# bubbledisplayfrontpack_v02.net
KiCad netlist of a schematic drawn in EAGLE
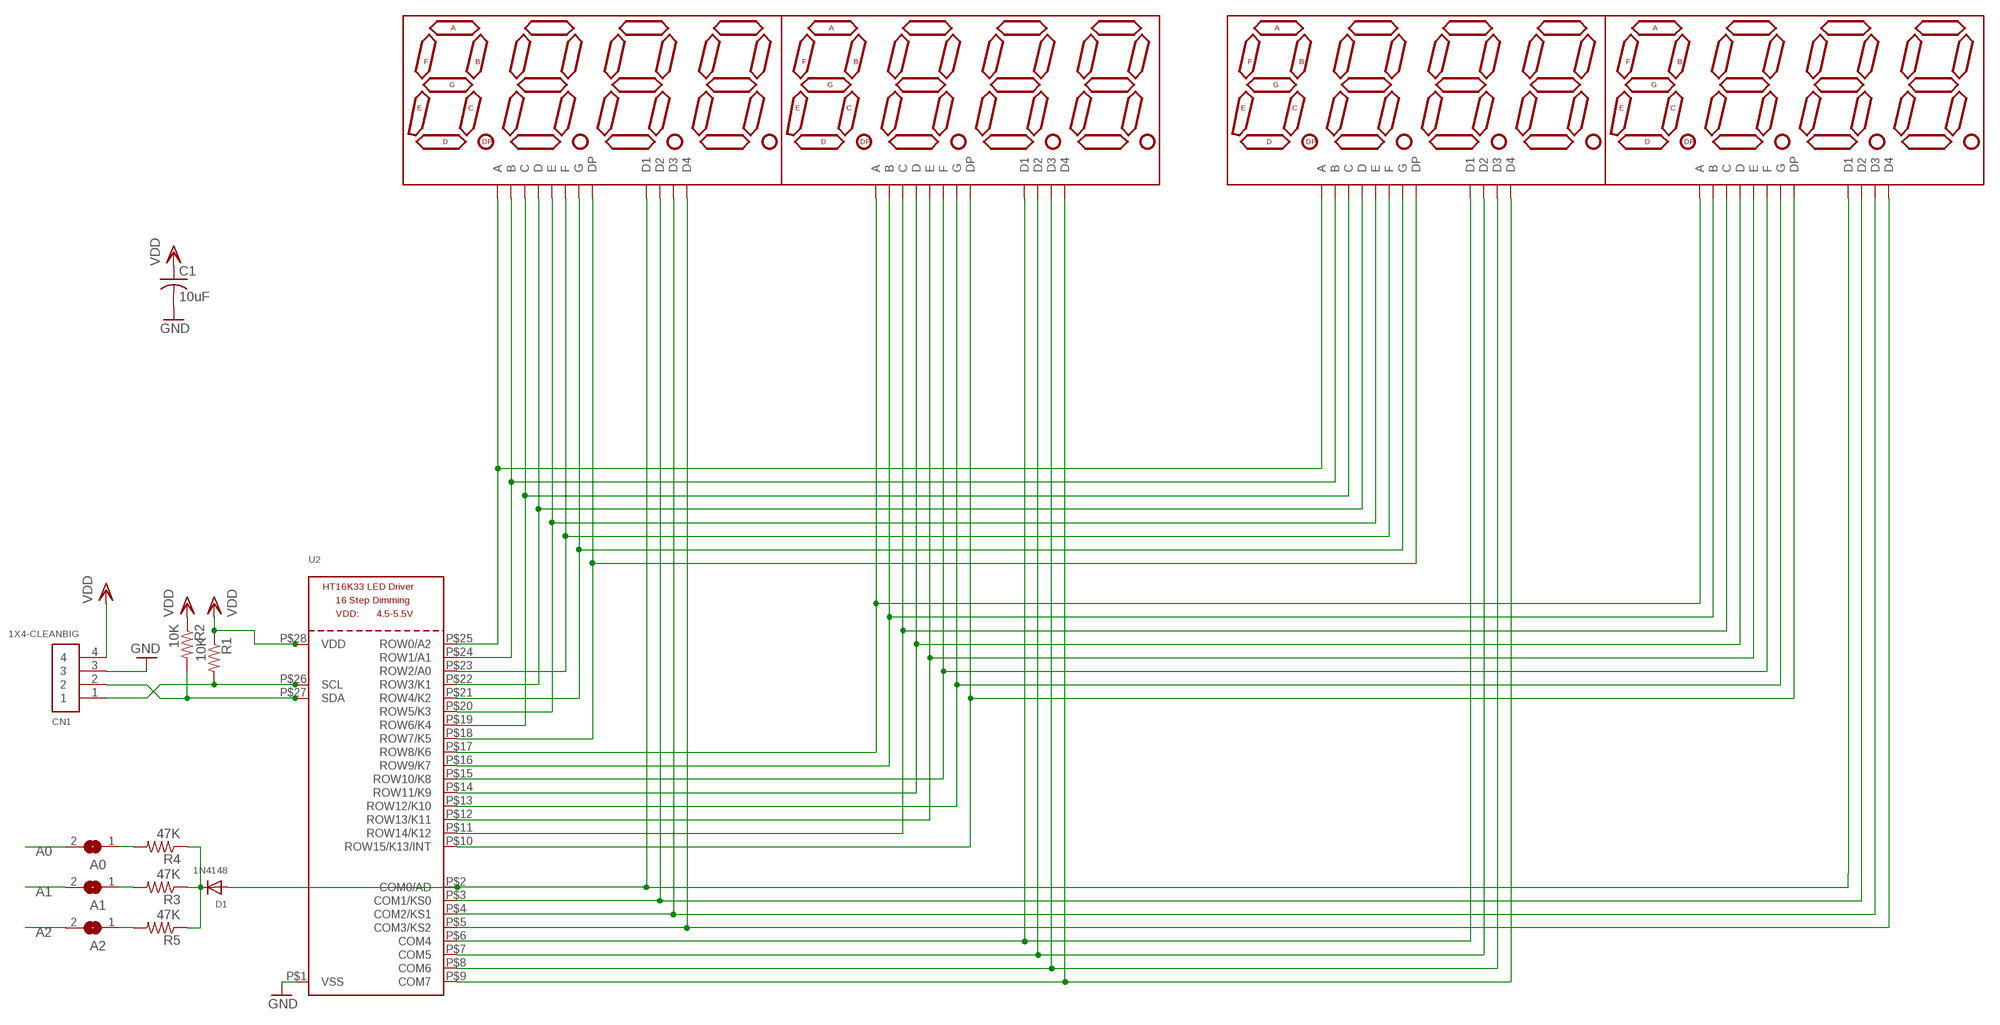
[diagram p0: schematic, sheet 1]

(export (version "E")
  (design (tool "Eeschema 10.0.6"))
  (components
    (comp (ref "A0")
      (value "SOLDERJUMPERREFLOW_NOPASTE")
      (footprint "eagle-import:SOLDERJUMPER_REFLOW_NOPASTE")
      (libsource (lib "eagle-import") (part "SOLDERJUMPERREFLOW_NOPASTE"))
    )
    (comp (ref "A1")
      (value "SOLDERJUMPERREFLOW_NOPASTE")
      (footprint "eagle-import:SOLDERJUMPER_REFLOW_NOPASTE")
      (libsource (lib "eagle-import") (part "SOLDERJUMPERREFLOW_NOPASTE"))
    )
    (comp (ref "A2")
      (value "SOLDERJUMPERREFLOW_NOPASTE")
      (footprint "eagle-import:SOLDERJUMPER_REFLOW_NOPASTE")
      (libsource (lib "eagle-import") (part "SOLDERJUMPERREFLOW_NOPASTE"))
    )
    (comp (ref "C1")
      (value "10uF")
      (footprint "eagle-import:C0805K")
      (libsource (lib "eagle-import") (part "C-USC0805K"))
    )
    (comp (ref "CN1")
      (value "1X4-CLEANBIG")
      (footprint "eagle-import:1X04-CLEANBIG")
      (libsource (lib "eagle-import") (part "1X4-CLEANBIG"))
    )
    (comp (ref "D1")
      (value "1N4148")
      (footprint "eagle-import:SOD-323F")
      (libsource (lib "eagle-import") (part "DIODESOD-323F"))
    )
    (comp (ref "DISPLAY1")
      (value "hp")
      (footprint "eagle-import:DIL12")
      (libsource (lib "eagle-import") (part "7-SEGMENT-4DIGIT-COUNTER-HP-BUBBLE"))
    )
    (comp (ref "DISPLAY2")
      (value "hp")
      (footprint "eagle-import:DIL12")
      (libsource (lib "eagle-import") (part "7-SEGMENT-4DIGIT-COUNTER-HP-BUBBLE"))
    )
    (comp (ref "DISPLAY3")
      (value "hp")
      (footprint "eagle-import:DIL12")
      (libsource (lib "eagle-import") (part "7-SEGMENT-4DIGIT-COUNTER-HP-BUBBLE"))
    )
    (comp (ref "DISPLAY4")
      (value "hp")
      (footprint "eagle-import:DIL12")
      (libsource (lib "eagle-import") (part "7-SEGMENT-4DIGIT-COUNTER-HP-BUBBLE"))
    )
    (comp (ref "R1")
      (value "10K")
      (footprint "eagle-import:R0805")
      (libsource (lib "eagle-import") (part "R-US_R0805"))
    )
    (comp (ref "R2")
      (value "10K")
      (footprint "eagle-import:R0805")
      (libsource (lib "eagle-import") (part "R-US_R0805"))
    )
    (comp (ref "R3")
      (value "47K")
      (footprint "eagle-import:R0805")
      (libsource (lib "eagle-import") (part "R-US_R0805"))
    )
    (comp (ref "R4")
      (value "47K")
      (footprint "eagle-import:R0805")
      (libsource (lib "eagle-import") (part "R-US_R0805"))
    )
    (comp (ref "R5")
      (value "47K")
      (footprint "eagle-import:R0805")
      (libsource (lib "eagle-import") (part "R-US_R0805"))
    )
    (comp (ref "U2")
      (value "HT16K33_SOP28")
      (footprint "eagle-import:SOP28_300MIL")
      (libsource (lib "eagle-import") (part "HT16K33_SOP28"))
    )
  )
  (nets
    (net (code "1") (name "/A0") (class "Default")
      (node (ref "A0") (pin "2") (pinfunction "2_2") (pintype "passive"))
      (node (ref "DISPLAY1") (pin "9") (pinfunction "F_9") (pintype "bidirectional"))
      (node (ref "DISPLAY3") (pin "9") (pinfunction "F_9") (pintype "bidirectional"))
      (node (ref "U2") (pin "P$23") (pinfunction "ROW2/A0_P$23") (pintype "bidirectional"))
    )
    (net (code "2") (name "/A1") (class "Default")
      (node (ref "A1") (pin "2") (pinfunction "2_2") (pintype "passive"))
      (node (ref "DISPLAY1") (pin "11") (pinfunction "B_11") (pintype "bidirectional"))
      (node (ref "DISPLAY3") (pin "11") (pinfunction "B_11") (pintype "bidirectional"))
      (node (ref "U2") (pin "P$24") (pinfunction "ROW1/A1_P$24") (pintype "bidirectional"))
    )
    (net (code "3") (name "/A2") (class "Default")
      (node (ref "A2") (pin "2") (pinfunction "2_2") (pintype "passive"))
      (node (ref "DISPLAY1") (pin "12") (pinfunction "A_12") (pintype "bidirectional"))
      (node (ref "DISPLAY3") (pin "12") (pinfunction "A_12") (pintype "bidirectional"))
      (node (ref "U2") (pin "P$25") (pinfunction "ROW0/A2_P$25") (pintype "bidirectional"))
    )
    (net (code "4") (name "GND") (class "Default")
      (node (ref "C1") (pin "2") (pinfunction "2_2") (pintype "passive"))
      (node (ref "CN1") (pin "3") (pinfunction "3_3") (pintype "bidirectional"))
      (node (ref "U2") (pin "P$1") (pinfunction "VSS_P$1") (pintype "bidirectional"))
    )
    (net (code "5") (name "Net-(A0-Pad1)") (class "Default")
      (node (ref "A0") (pin "1") (pinfunction "1_1") (pintype "passive"))
      (node (ref "R4") (pin "2") (pinfunction "2_2") (pintype "passive"))
    )
    (net (code "6") (name "Net-(A1-Pad1)") (class "Default")
      (node (ref "A1") (pin "1") (pinfunction "1_1") (pintype "passive"))
      (node (ref "R3") (pin "2") (pinfunction "2_2") (pintype "passive"))
    )
    (net (code "7") (name "Net-(A2-Pad1)") (class "Default")
      (node (ref "A2") (pin "1") (pinfunction "1_1") (pintype "passive"))
      (node (ref "R5") (pin "2") (pinfunction "2_2") (pintype "passive"))
    )
    (net (code "8") (name "Net-(D1-PadC)") (class "Default")
      (node (ref "D1") (pin "C") (pinfunction "C_C") (pintype "passive"))
      (node (ref "R3") (pin "1") (pinfunction "1_1") (pintype "passive"))
      (node (ref "R4") (pin "1") (pinfunction "1_1") (pintype "passive"))
      (node (ref "R5") (pin "1") (pinfunction "1_1") (pintype "passive"))
    )
    (net (code "9") (name "Net-(DISPLAY1-C)") (class "Default")
      (node (ref "DISPLAY1") (pin "3") (pinfunction "C_3") (pintype "bidirectional"))
      (node (ref "DISPLAY3") (pin "3") (pinfunction "C_3") (pintype "bidirectional"))
      (node (ref "U2") (pin "P$19") (pinfunction "ROW6/K4_P$19") (pintype "bidirectional"))
    )
    (net (code "10") (name "Net-(DISPLAY1-D)") (class "Default")
      (node (ref "DISPLAY1") (pin "8") (pinfunction "D_8") (pintype "bidirectional"))
      (node (ref "DISPLAY3") (pin "8") (pinfunction "D_8") (pintype "bidirectional"))
      (node (ref "U2") (pin "P$22") (pinfunction "ROW3/K1_P$22") (pintype "bidirectional"))
    )
    (net (code "11") (name "Net-(DISPLAY1-D1)") (class "Default")
      (node (ref "DISPLAY1") (pin "1") (pinfunction "D1_1") (pintype "bidirectional"))
      (node (ref "DISPLAY4") (pin "1") (pinfunction "D1_1") (pintype "bidirectional"))
      (node (ref "U2") (pin "P$6") (pinfunction "COM4_P$6") (pintype "bidirectional"))
    )
    (net (code "12") (name "Net-(DISPLAY1-D2)") (class "Default")
      (node (ref "DISPLAY1") (pin "10") (pinfunction "D2_10") (pintype "bidirectional"))
      (node (ref "DISPLAY4") (pin "10") (pinfunction "D2_10") (pintype "bidirectional"))
      (node (ref "U2") (pin "P$7") (pinfunction "COM5_P$7") (pintype "bidirectional"))
    )
    (net (code "13") (name "Net-(DISPLAY1-D3)") (class "Default")
      (node (ref "DISPLAY1") (pin "4") (pinfunction "D3_4") (pintype "bidirectional"))
      (node (ref "DISPLAY4") (pin "4") (pinfunction "D3_4") (pintype "bidirectional"))
      (node (ref "U2") (pin "P$8") (pinfunction "COM6_P$8") (pintype "bidirectional"))
    )
    (net (code "14") (name "Net-(DISPLAY1-D4)") (class "Default")
      (node (ref "DISPLAY1") (pin "6") (pinfunction "D4_6") (pintype "bidirectional"))
      (node (ref "DISPLAY4") (pin "6") (pinfunction "D4_6") (pintype "bidirectional"))
      (node (ref "U2") (pin "P$9") (pinfunction "COM7_P$9") (pintype "bidirectional"))
    )
    (net (code "15") (name "Net-(DISPLAY1-DP)") (class "Default")
      (node (ref "DISPLAY1") (pin "5") (pinfunction "DP_5") (pintype "bidirectional"))
      (node (ref "DISPLAY3") (pin "5") (pinfunction "DP_5") (pintype "bidirectional"))
      (node (ref "U2") (pin "P$18") (pinfunction "ROW7/K5_P$18") (pintype "bidirectional"))
    )
    (net (code "16") (name "Net-(DISPLAY1-E)") (class "Default")
      (node (ref "DISPLAY1") (pin "2") (pinfunction "E_2") (pintype "bidirectional"))
      (node (ref "DISPLAY3") (pin "2") (pinfunction "E_2") (pintype "bidirectional"))
      (node (ref "U2") (pin "P$20") (pinfunction "ROW5/K3_P$20") (pintype "bidirectional"))
    )
    (net (code "17") (name "Net-(DISPLAY1-G)") (class "Default")
      (node (ref "DISPLAY1") (pin "7") (pinfunction "G_7") (pintype "bidirectional"))
      (node (ref "DISPLAY3") (pin "7") (pinfunction "G_7") (pintype "bidirectional"))
      (node (ref "U2") (pin "P$21") (pinfunction "ROW4/K2_P$21") (pintype "bidirectional"))
    )
    (net (code "18") (name "Net-(DISPLAY2-A)") (class "Default")
      (node (ref "DISPLAY2") (pin "12") (pinfunction "A_12") (pintype "bidirectional"))
      (node (ref "DISPLAY4") (pin "12") (pinfunction "A_12") (pintype "bidirectional"))
      (node (ref "U2") (pin "P$17") (pinfunction "ROW8/K6_P$17") (pintype "bidirectional"))
    )
    (net (code "19") (name "Net-(DISPLAY2-B)") (class "Default")
      (node (ref "DISPLAY2") (pin "11") (pinfunction "B_11") (pintype "bidirectional"))
      (node (ref "DISPLAY4") (pin "11") (pinfunction "B_11") (pintype "bidirectional"))
      (node (ref "U2") (pin "P$16") (pinfunction "ROW9/K7_P$16") (pintype "bidirectional"))
    )
    (net (code "20") (name "Net-(DISPLAY2-C)") (class "Default")
      (node (ref "DISPLAY2") (pin "3") (pinfunction "C_3") (pintype "bidirectional"))
      (node (ref "DISPLAY4") (pin "3") (pinfunction "C_3") (pintype "bidirectional"))
      (node (ref "U2") (pin "P$11") (pinfunction "ROW14/K12_P$11") (pintype "bidirectional"))
    )
    (net (code "21") (name "Net-(DISPLAY2-D)") (class "Default")
      (node (ref "DISPLAY2") (pin "8") (pinfunction "D_8") (pintype "bidirectional"))
      (node (ref "DISPLAY4") (pin "8") (pinfunction "D_8") (pintype "bidirectional"))
      (node (ref "U2") (pin "P$14") (pinfunction "ROW11/K9_P$14") (pintype "bidirectional"))
    )
    (net (code "22") (name "Net-(DISPLAY2-D1)") (class "Default")
      (node (ref "D1") (pin "A") (pinfunction "A_A") (pintype "passive"))
      (node (ref "DISPLAY2") (pin "1") (pinfunction "D1_1") (pintype "bidirectional"))
      (node (ref "DISPLAY3") (pin "1") (pinfunction "D1_1") (pintype "bidirectional"))
      (node (ref "U2") (pin "P$2") (pinfunction "COM0/AD_P$2") (pintype "bidirectional"))
    )
    (net (code "23") (name "Net-(DISPLAY2-D2)") (class "Default")
      (node (ref "DISPLAY2") (pin "10") (pinfunction "D2_10") (pintype "bidirectional"))
      (node (ref "DISPLAY3") (pin "10") (pinfunction "D2_10") (pintype "bidirectional"))
      (node (ref "U2") (pin "P$3") (pinfunction "COM1/KS0_P$3") (pintype "bidirectional"))
    )
    (net (code "24") (name "Net-(DISPLAY2-D3)") (class "Default")
      (node (ref "DISPLAY2") (pin "4") (pinfunction "D3_4") (pintype "bidirectional"))
      (node (ref "DISPLAY3") (pin "4") (pinfunction "D3_4") (pintype "bidirectional"))
      (node (ref "U2") (pin "P$4") (pinfunction "COM2/KS1_P$4") (pintype "bidirectional"))
    )
    (net (code "25") (name "Net-(DISPLAY2-D4)") (class "Default")
      (node (ref "DISPLAY2") (pin "6") (pinfunction "D4_6") (pintype "bidirectional"))
      (node (ref "DISPLAY3") (pin "6") (pinfunction "D4_6") (pintype "bidirectional"))
      (node (ref "U2") (pin "P$5") (pinfunction "COM3/KS2_P$5") (pintype "bidirectional"))
    )
    (net (code "26") (name "Net-(DISPLAY2-DP)") (class "Default")
      (node (ref "DISPLAY2") (pin "5") (pinfunction "DP_5") (pintype "bidirectional"))
      (node (ref "DISPLAY4") (pin "5") (pinfunction "DP_5") (pintype "bidirectional"))
      (node (ref "U2") (pin "P$10") (pinfunction "ROW15/K13/INT_P$10") (pintype "bidirectional"))
    )
    (net (code "27") (name "Net-(DISPLAY2-E)") (class "Default")
      (node (ref "DISPLAY2") (pin "2") (pinfunction "E_2") (pintype "bidirectional"))
      (node (ref "DISPLAY4") (pin "2") (pinfunction "E_2") (pintype "bidirectional"))
      (node (ref "U2") (pin "P$12") (pinfunction "ROW13/K11_P$12") (pintype "bidirectional"))
    )
    (net (code "28") (name "Net-(DISPLAY2-F)") (class "Default")
      (node (ref "DISPLAY2") (pin "9") (pinfunction "F_9") (pintype "bidirectional"))
      (node (ref "DISPLAY4") (pin "9") (pinfunction "F_9") (pintype "bidirectional"))
      (node (ref "U2") (pin "P$15") (pinfunction "ROW10/K8_P$15") (pintype "bidirectional"))
    )
    (net (code "29") (name "Net-(DISPLAY2-G)") (class "Default")
      (node (ref "DISPLAY2") (pin "7") (pinfunction "G_7") (pintype "bidirectional"))
      (node (ref "DISPLAY4") (pin "7") (pinfunction "G_7") (pintype "bidirectional"))
      (node (ref "U2") (pin "P$13") (pinfunction "ROW12/K10_P$13") (pintype "bidirectional"))
    )
    (net (code "30") (name "Net-(U2-SCL)") (class "Default")
      (node (ref "CN1") (pin "1") (pinfunction "1_1") (pintype "bidirectional"))
      (node (ref "R1") (pin "2") (pinfunction "2_2") (pintype "passive"))
      (node (ref "U2") (pin "P$26") (pinfunction "SCL_P$26") (pintype "bidirectional"))
    )
    (net (code "31") (name "Net-(U2-SDA)") (class "Default")
      (node (ref "CN1") (pin "2") (pinfunction "2_2") (pintype "bidirectional"))
      (node (ref "R2") (pin "2") (pinfunction "2_2") (pintype "passive"))
      (node (ref "U2") (pin "P$27") (pinfunction "SDA_P$27") (pintype "bidirectional"))
    )
    (net (code "32") (name "VDD") (class "Default")
      (node (ref "C1") (pin "1") (pinfunction "1_1") (pintype "passive"))
      (node (ref "CN1") (pin "4") (pinfunction "4_4") (pintype "bidirectional"))
      (node (ref "R1") (pin "1") (pinfunction "1_1") (pintype "passive"))
      (node (ref "R2") (pin "1") (pinfunction "1_1") (pintype "passive"))
      (node (ref "U2") (pin "P$28") (pinfunction "VDD_P$28") (pintype "bidirectional"))
    )
  )
)
